# Network.net
KiCad netlist of a schematic drawn in Altium Designer
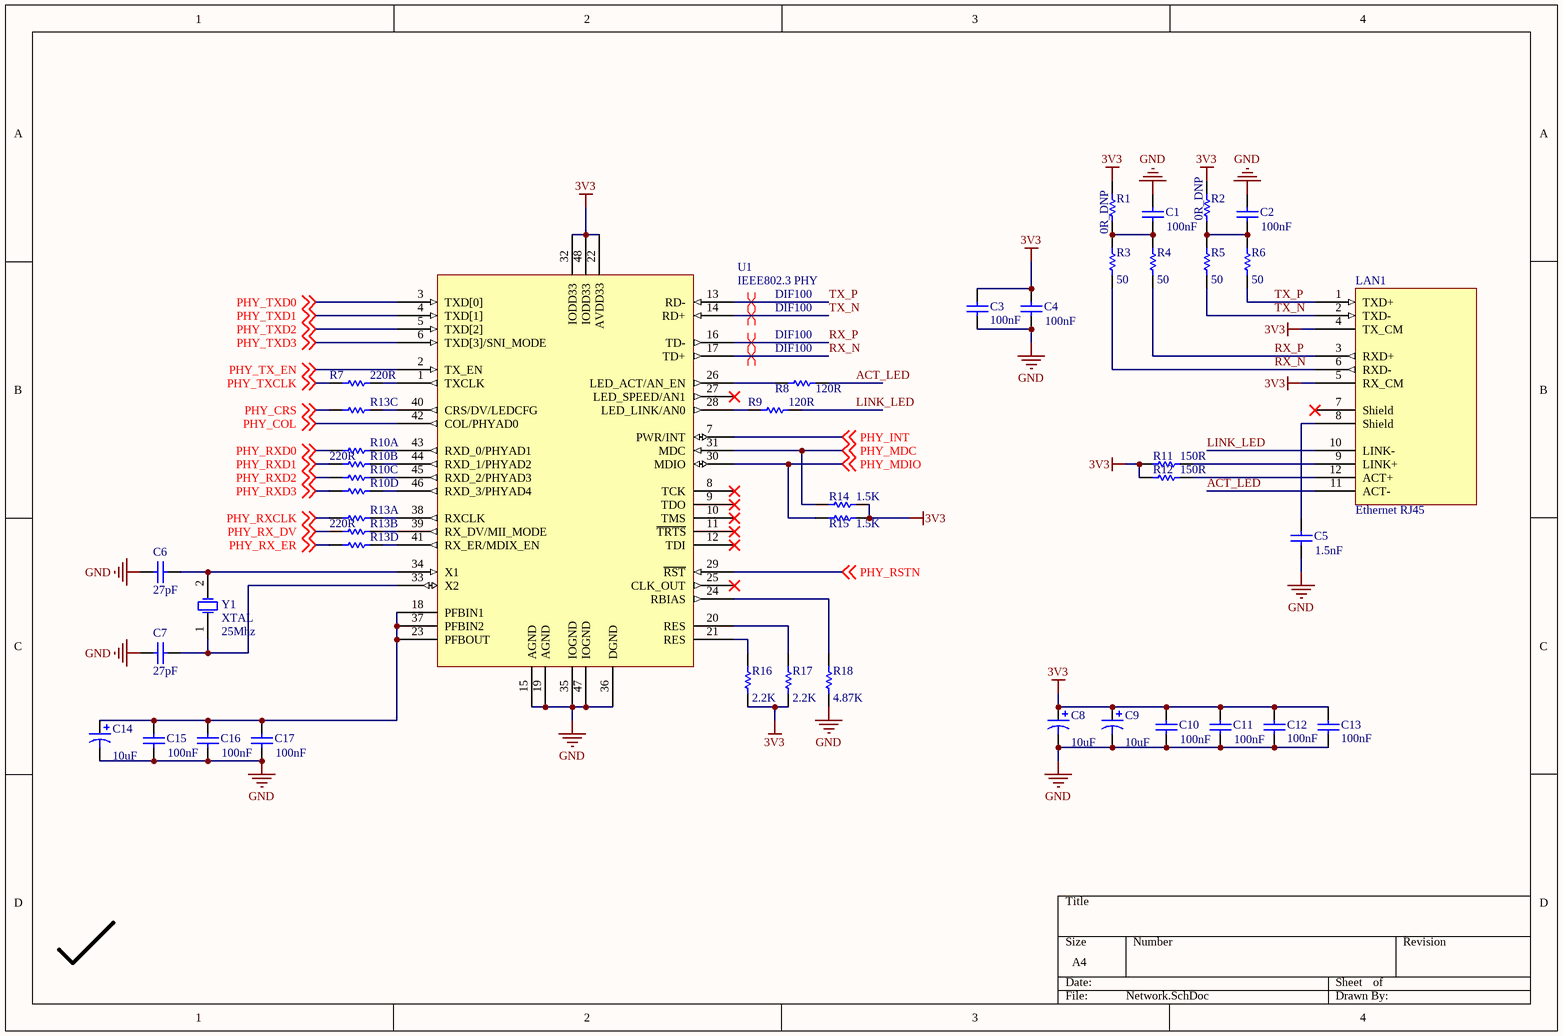
[diagram p0: Network.SchDoc]

(export (version "E")
  (design (tool "Eeschema 10.0.6"))
  (components
    (comp (ref "C1")
      (value "100nF")
      (footprint "0603PKG")
      (description "Capacitor")
      (fields (field (name "Comment") "Cap") (field (name "PUBLISHER") "Altium Limited"))
      (libsource (lib "Miscellaneous Devices") (part "Cap"))
    )
    (comp (ref "C2")
      (value "100nF")
      (footprint "0603PKG")
      (description "Capacitor")
      (fields (field (name "Comment") "Cap") (field (name "PUBLISHER") "Altium Limited"))
      (libsource (lib "Miscellaneous Devices") (part "Cap"))
    )
    (comp (ref "C3")
      (value "100nF")
      (footprint "0603PKG")
      (description "Capacitor")
      (fields (field (name "Comment") "Cap") (field (name "PUBLISHER") "Altium Limited"))
      (libsource (lib "Miscellaneous Devices") (part "Cap"))
    )
    (comp (ref "C4")
      (value "100nF")
      (footprint "0603PKG")
      (description "Capacitor")
      (fields (field (name "Comment") "Cap") (field (name "PUBLISHER") "Altium Limited"))
      (libsource (lib "Miscellaneous Devices") (part "Cap"))
    )
    (comp (ref "C5")
      (value "1.5nF")
      (footprint "C0805")
      (description "Capacitor")
      (fields (field (name "Comment") "Cap") (field (name "PUBLISHER") "Altium Limited"))
      (libsource (lib "Miscellaneous Devices") (part "Cap"))
    )
    (comp (ref "C6")
      (value "27pF")
      (footprint "C0805")
      (description "Capacitor")
      (fields (field (name "Comment") "Cap") (field (name "PUBLISHER") "Altium Limited"))
      (libsource (lib "Miscellaneous Devices") (part "Cap"))
    )
    (comp (ref "C7")
      (value "27pF")
      (footprint "C0805")
      (description "Capacitor")
      (fields (field (name "Comment") "Cap") (field (name "PUBLISHER") "Altium Limited"))
      (libsource (lib "Miscellaneous Devices") (part "Cap"))
    )
    (comp (ref "C8")
      (value "10uF")
      (footprint "3216X18N")
      (description "Polarized Capacitor (Surface Mount)")
      (fields (field (name "Comment") "Cap Pol3") (field (name "PUBLISHER") "Altium Limited"))
      (libsource (lib "Miscellaneous Devices") (part "Cap Pol3"))
    )
    (comp (ref "C9")
      (value "10uF")
      (footprint "3216X18N")
      (description "Polarized Capacitor (Surface Mount)")
      (fields (field (name "Comment") "Cap Pol3") (field (name "PUBLISHER") "Altium Limited"))
      (libsource (lib "Miscellaneous Devices") (part "Cap Pol3"))
    )
    (comp (ref "C10")
      (value "100nF")
      (footprint "0603PKG")
      (description "Capacitor")
      (fields (field (name "Comment") "Cap") (field (name "PUBLISHER") "Altium Limited"))
      (libsource (lib "Miscellaneous Devices") (part "Cap"))
    )
    (comp (ref "C11")
      (value "100nF")
      (footprint "0603PKG")
      (description "Capacitor")
      (fields (field (name "Comment") "Cap") (field (name "PUBLISHER") "Altium Limited"))
      (libsource (lib "Miscellaneous Devices") (part "Cap"))
    )
    (comp (ref "C12")
      (value "100nF")
      (footprint "0603PKG")
      (description "Capacitor")
      (fields (field (name "Comment") "Cap") (field (name "PUBLISHER") "Altium Limited"))
      (libsource (lib "Miscellaneous Devices") (part "Cap"))
    )
    (comp (ref "C13")
      (value "100nF")
      (footprint "0603PKG")
      (description "Capacitor")
      (fields (field (name "Comment") "Cap") (field (name "PUBLISHER") "Altium Limited"))
      (libsource (lib "Miscellaneous Devices") (part "Cap"))
    )
    (comp (ref "C14")
      (value "10uF")
      (footprint "3216X18N")
      (description "Polarized Capacitor (Surface Mount)")
      (fields (field (name "Comment") "Cap Pol3") (field (name "PUBLISHER") "Altium Limited"))
      (libsource (lib "Miscellaneous Devices") (part "Cap Pol3"))
    )
    (comp (ref "C15")
      (value "100nF")
      (footprint "0603PKG")
      (description "Capacitor")
      (fields (field (name "Comment") "Cap") (field (name "PUBLISHER") "Altium Limited"))
      (libsource (lib "Miscellaneous Devices") (part "Cap"))
    )
    (comp (ref "C16")
      (value "100nF")
      (footprint "0603PKG")
      (description "Capacitor")
      (fields (field (name "Comment") "Cap") (field (name "PUBLISHER") "Altium Limited"))
      (libsource (lib "Miscellaneous Devices") (part "Cap"))
    )
    (comp (ref "C17")
      (value "100nF")
      (footprint "0603PKG")
      (description "Capacitor")
      (fields (field (name "Comment") "Cap") (field (name "PUBLISHER") "Altium Limited"))
      (libsource (lib "Miscellaneous Devices") (part "Cap"))
    )
    (comp (ref "LAN1")
      (value "Ethernet RJ45")
      (footprint "RJ45")
      (libsource (lib "DE0_IntLib_Schem") (part "Ethernet_RJ45"))
    )
    (comp (ref "R1")
      (value "0R_DNP")
      (footprint "C0805")
      (description "Semiconductor Resistor")
      (fields (field (name "Comment") "Res Semi") (field (name "PUBLISHER") "Altium Limited"))
      (libsource (lib "Miscellaneous Devices") (part "Res Semi"))
    )
    (comp (ref "R2")
      (value "0R_DNP")
      (footprint "C0805")
      (description "Semiconductor Resistor")
      (fields (field (name "Comment") "Res Semi") (field (name "PUBLISHER") "Altium Limited"))
      (libsource (lib "Miscellaneous Devices") (part "Res Semi"))
    )
    (comp (ref "R3")
      (value "50")
      (footprint "C0805")
      (description "Semiconductor Resistor")
      (fields (field (name "Comment") "Res Semi") (field (name "PUBLISHER") "Altium Limited"))
      (libsource (lib "Miscellaneous Devices") (part "Res Semi"))
    )
    (comp (ref "R4")
      (value "50")
      (footprint "C0805")
      (description "Semiconductor Resistor")
      (fields (field (name "Comment") "Res Semi") (field (name "PUBLISHER") "Altium Limited"))
      (libsource (lib "Miscellaneous Devices") (part "Res Semi"))
    )
    (comp (ref "R5")
      (value "50")
      (footprint "C0805")
      (description "Semiconductor Resistor")
      (fields (field (name "Comment") "Res Semi") (field (name "PUBLISHER") "Altium Limited"))
      (libsource (lib "Miscellaneous Devices") (part "Res Semi"))
    )
    (comp (ref "R6")
      (value "50")
      (footprint "C0805")
      (description "Semiconductor Resistor")
      (fields (field (name "Comment") "Res Semi") (field (name "PUBLISHER") "Altium Limited"))
      (libsource (lib "Miscellaneous Devices") (part "Res Semi"))
    )
    (comp (ref "R7")
      (value "220R")
      (footprint "0603PKG")
      (description "Semiconductor Resistor")
      (fields (field (name "Comment") "Res Semi") (field (name "PUBLISHER") "Altium Limited"))
      (libsource (lib "Miscellaneous Devices") (part "Res Semi"))
    )
    (comp (ref "R8")
      (value "120R")
      (footprint "C0805")
      (description "Semiconductor Resistor")
      (fields (field (name "Comment") "Res Semi") (field (name "PUBLISHER") "Altium Limited"))
      (libsource (lib "Miscellaneous Devices") (part "Res Semi"))
    )
    (comp (ref "R9")
      (value "120R")
      (footprint "C0805")
      (description "Semiconductor Resistor")
      (fields (field (name "Comment") "Res Semi") (field (name "PUBLISHER") "Altium Limited"))
      (libsource (lib "Miscellaneous Devices") (part "Res Semi"))
    )
    (comp (ref "R10")
      (value "220R")
      (footprint "ARA4x0603")
      (fields (field (name "Comment") "ChipArray_4x"))
      (libsource (lib "Connector_IntLib") (part "ChipArray_4x"))
    )
    (comp (ref "R11")
      (value "150R")
      (footprint "C0805")
      (description "Semiconductor Resistor")
      (fields (field (name "Comment") "Res Semi") (field (name "PUBLISHER") "Altium Limited"))
      (libsource (lib "Miscellaneous Devices") (part "Res Semi"))
    )
    (comp (ref "R12")
      (value "150R")
      (footprint "C0805")
      (description "Semiconductor Resistor")
      (fields (field (name "Comment") "Res Semi") (field (name "PUBLISHER") "Altium Limited"))
      (libsource (lib "Miscellaneous Devices") (part "Res Semi"))
    )
    (comp (ref "R13")
      (value "220R")
      (footprint "ARA4x0603")
      (fields (field (name "Comment") "ChipArray_4x"))
      (libsource (lib "Connector_IntLib") (part "ChipArray_4x"))
    )
    (comp (ref "R14")
      (value "1.5K")
      (footprint "0603PKG")
      (description "Semiconductor Resistor")
      (fields (field (name "Comment") "Res Semi") (field (name "PUBLISHER") "Altium Limited"))
      (libsource (lib "Miscellaneous Devices") (part "Res Semi"))
    )
    (comp (ref "R15")
      (value "1.5K")
      (footprint "0603PKG")
      (description "Semiconductor Resistor")
      (fields (field (name "Comment") "Res Semi") (field (name "PUBLISHER") "Altium Limited"))
      (libsource (lib "Miscellaneous Devices") (part "Res Semi"))
    )
    (comp (ref "R16")
      (value "2.2K")
      (footprint "0603PKG")
      (description "Semiconductor Resistor")
      (fields (field (name "Comment") "Res Semi") (field (name "PUBLISHER") "Altium Limited"))
      (libsource (lib "Miscellaneous Devices") (part "Res Semi"))
    )
    (comp (ref "R17")
      (value "2.2K")
      (footprint "0603PKG")
      (description "Semiconductor Resistor")
      (fields (field (name "Comment") "Res Semi") (field (name "PUBLISHER") "Altium Limited"))
      (libsource (lib "Miscellaneous Devices") (part "Res Semi"))
    )
    (comp (ref "R18")
      (value "4.87K")
      (footprint "C1206")
      (description "Semiconductor Resistor")
      (fields (field (name "Comment") "Res Semi") (field (name "PUBLISHER") "Altium Limited"))
      (libsource (lib "Miscellaneous Devices") (part "Res Semi"))
    )
    (comp (ref "U1")
      (value "IEEE802.3 PHY")
      (footprint "LQFP48")
      (libsource (lib "Conn_Schlib") (part "DP83848C"))
    )
    (comp (ref "Y1")
      (value "XTAL")
      (footprint "SMD_Crystal")
      (description "Crystal Oscillator")
      (fields (field (name "ALTIUM_VALUE") "25Mhz") (field (name "PUBLISHER") "Altium Limited"))
      (libsource (lib "Miscellaneous Devices") (part "XTAL"))
    )
  )
  (nets
    (net (code "1") (name "/ACT_LED") (class "Default")
      (node (ref "LAN1") (pin "11") (pinfunction "ACT-_11") (pintype "power_in"))
      (node (ref "R8") (pin "2") (pinfunction "2_2") (pintype "passive"))
    )
    (net (code "2") (name "/LINK_LED") (class "Default")
      (node (ref "LAN1") (pin "10") (pinfunction "LINK-_10") (pintype "power_in"))
      (node (ref "R9") (pin "2") (pinfunction "2_2") (pintype "passive"))
    )
    (net (code "3") (name "/RX_N") (class "Default")
      (node (ref "LAN1") (pin "6") (pinfunction "RXD-_6") (pintype "output"))
      (node (ref "R3") (pin "1") (pinfunction "1_1") (pintype "passive"))
      (node (ref "U1") (pin "17") (pinfunction "TD+_17") (pintype "output"))
    )
    (net (code "4") (name "/RX_P") (class "Default")
      (node (ref "LAN1") (pin "3") (pinfunction "RXD+_3") (pintype "output"))
      (node (ref "R4") (pin "1") (pinfunction "1_1") (pintype "passive"))
      (node (ref "U1") (pin "16") (pinfunction "TD-_16") (pintype "output"))
    )
    (net (code "5") (name "/TX_N") (class "Default")
      (node (ref "LAN1") (pin "2") (pinfunction "TXD-_2") (pintype "input"))
      (node (ref "R5") (pin "1") (pinfunction "1_1") (pintype "passive"))
      (node (ref "U1") (pin "14") (pinfunction "RD+_14") (pintype "input"))
    )
    (net (code "6") (name "/TX_P") (class "Default")
      (node (ref "LAN1") (pin "1") (pinfunction "TXD+_1") (pintype "input"))
      (node (ref "R6") (pin "1") (pinfunction "1_1") (pintype "passive"))
      (node (ref "U1") (pin "13") (pinfunction "RD-_13") (pintype "input"))
    )
    (net (code "7") (name "3V3") (class "Default")
      (node (ref "C10") (pin "2") (pinfunction "2_2") (pintype "passive"))
      (node (ref "C11") (pin "2") (pinfunction "2_2") (pintype "passive"))
      (node (ref "C12") (pin "2") (pinfunction "2_2") (pintype "passive"))
      (node (ref "C13") (pin "2") (pinfunction "2_2") (pintype "passive"))
      (node (ref "C3") (pin "1") (pinfunction "1_1") (pintype "passive"))
      (node (ref "C4") (pin "2") (pinfunction "2_2") (pintype "passive"))
      (node (ref "C8") (pin "1") (pinfunction "1_1") (pintype "passive"))
      (node (ref "C9") (pin "1") (pinfunction "1_1") (pintype "passive"))
      (node (ref "LAN1") (pin "4") (pinfunction "TX_CM_4") (pintype "power_in"))
      (node (ref "LAN1") (pin "5") (pinfunction "RX_CM_5") (pintype "power_in"))
      (node (ref "R1") (pin "2") (pinfunction "2_2") (pintype "passive"))
      (node (ref "R11") (pin "1") (pinfunction "1_1") (pintype "passive"))
      (node (ref "R12") (pin "1") (pinfunction "1_1") (pintype "passive"))
      (node (ref "R14") (pin "2") (pinfunction "2_2") (pintype "passive"))
      (node (ref "R15") (pin "1") (pinfunction "1_1") (pintype "passive"))
      (node (ref "R16") (pin "1") (pinfunction "1_1") (pintype "passive"))
      (node (ref "R17") (pin "1") (pinfunction "1_1") (pintype "passive"))
      (node (ref "R2") (pin "2") (pinfunction "2_2") (pintype "passive"))
      (node (ref "U1") (pin "22") (pinfunction "AVDD33_22") (pintype "power_in"))
      (node (ref "U1") (pin "32") (pinfunction "IODD33_32") (pintype "power_in"))
      (node (ref "U1") (pin "48") (pinfunction "IODD33_48") (pintype "power_in"))
    )
    (net (code "8") (name "GND") (class "Default")
      (node (ref "C1") (pin "2") (pinfunction "2_2") (pintype "passive"))
      (node (ref "C10") (pin "1") (pinfunction "1_1") (pintype "passive"))
      (node (ref "C11") (pin "1") (pinfunction "1_1") (pintype "passive"))
      (node (ref "C12") (pin "1") (pinfunction "1_1") (pintype "passive"))
      (node (ref "C13") (pin "1") (pinfunction "1_1") (pintype "passive"))
      (node (ref "C14") (pin "2") (pinfunction "2_2") (pintype "passive"))
      (node (ref "C15") (pin "1") (pinfunction "1_1") (pintype "passive"))
      (node (ref "C16") (pin "1") (pinfunction "1_1") (pintype "passive"))
      (node (ref "C17") (pin "1") (pinfunction "1_1") (pintype "passive"))
      (node (ref "C2") (pin "2") (pinfunction "2_2") (pintype "passive"))
      (node (ref "C3") (pin "2") (pinfunction "2_2") (pintype "passive"))
      (node (ref "C4") (pin "1") (pinfunction "1_1") (pintype "passive"))
      (node (ref "C5") (pin "1") (pinfunction "1_1") (pintype "passive"))
      (node (ref "C6") (pin "2") (pinfunction "2_2") (pintype "passive"))
      (node (ref "C7") (pin "2") (pinfunction "2_2") (pintype "passive"))
      (node (ref "C8") (pin "2") (pinfunction "2_2") (pintype "passive"))
      (node (ref "C9") (pin "2") (pinfunction "2_2") (pintype "passive"))
      (node (ref "R18") (pin "1") (pinfunction "1_1") (pintype "passive"))
      (node (ref "U1") (pin "15") (pinfunction "AGND_15") (pintype "power_in"))
      (node (ref "U1") (pin "19") (pinfunction "AGND_19") (pintype "power_in"))
      (node (ref "U1") (pin "35") (pinfunction "IOGND_35") (pintype "power_in"))
      (node (ref "U1") (pin "36") (pinfunction "DGND_36") (pintype "power_in"))
      (node (ref "U1") (pin "47") (pinfunction "IOGND_47") (pintype "power_in"))
    )
    (net (code "9") (name "Net-(C1-Pad1)") (class "Default")
      (node (ref "C1") (pin "1") (pinfunction "1_1") (pintype "passive"))
      (node (ref "R1") (pin "1") (pinfunction "1_1") (pintype "passive"))
      (node (ref "R3") (pin "2") (pinfunction "2_2") (pintype "passive"))
      (node (ref "R4") (pin "2") (pinfunction "2_2") (pintype "passive"))
    )
    (net (code "10") (name "Net-(C2-Pad1)") (class "Default")
      (node (ref "C2") (pin "1") (pinfunction "1_1") (pintype "passive"))
      (node (ref "R2") (pin "1") (pinfunction "1_1") (pintype "passive"))
      (node (ref "R5") (pin "2") (pinfunction "2_2") (pintype "passive"))
      (node (ref "R6") (pin "2") (pinfunction "2_2") (pintype "passive"))
    )
    (net (code "11") (name "Net-(C5-Pad2)") (class "Default")
      (node (ref "C5") (pin "2") (pinfunction "2_2") (pintype "passive"))
      (node (ref "LAN1") (pin "8") (pinfunction "Shield_8") (pintype "passive"))
    )
    (net (code "12") (name "Net-(LAN1-ACT+)") (class "Default")
      (node (ref "LAN1") (pin "12") (pinfunction "ACT+_12") (pintype "power_in"))
      (node (ref "R12") (pin "2") (pinfunction "2_2") (pintype "passive"))
    )
    (net (code "13") (name "Net-(LAN1-LINK+)") (class "Default")
      (node (ref "LAN1") (pin "9") (pinfunction "LINK+_9") (pintype "power_in"))
      (node (ref "R11") (pin "2") (pinfunction "2_2") (pintype "passive"))
    )
    (net (code "14") (name "Net-(R16-Pad2)") (class "Default")
      (node (ref "R16") (pin "2") (pinfunction "2_2") (pintype "passive"))
      (node (ref "U1") (pin "21") (pinfunction "RES_21") (pintype "passive"))
    )
    (net (code "15") (name "Net-(R17-Pad2)") (class "Default")
      (node (ref "R17") (pin "2") (pinfunction "2_2") (pintype "passive"))
      (node (ref "U1") (pin "20") (pinfunction "RES_20") (pintype "passive"))
    )
    (net (code "16") (name "Net-(U1-CRS{slash}DV{slash}LEDCFG)") (class "Default")
      (node (ref "R13") (pin "6") (pinfunction "R3_6") (pintype "passive"))
      (node (ref "U1") (pin "40") (pinfunction "CRS/DV/LEDCFG_40") (pintype "output"))
    )
    (net (code "17") (name "Net-(U1-LED_ACT{slash}AN_EN)") (class "Default")
      (node (ref "R8") (pin "1") (pinfunction "1_1") (pintype "passive"))
      (node (ref "U1") (pin "26") (pinfunction "LED_ACT/AN_EN_26") (pintype "output"))
    )
    (net (code "18") (name "Net-(U1-LED_LINK{slash}AN0)") (class "Default")
      (node (ref "R9") (pin "1") (pinfunction "1_1") (pintype "passive"))
      (node (ref "U1") (pin "28") (pinfunction "LED_LINK/AN0_28") (pintype "output"))
    )
    (net (code "19") (name "Net-(U1-PFBIN1)") (class "Default")
      (node (ref "C14") (pin "1") (pinfunction "1_1") (pintype "passive"))
      (node (ref "C15") (pin "2") (pinfunction "2_2") (pintype "passive"))
      (node (ref "C16") (pin "2") (pinfunction "2_2") (pintype "passive"))
      (node (ref "C17") (pin "2") (pinfunction "2_2") (pintype "passive"))
      (node (ref "U1") (pin "18") (pinfunction "PFBIN1_18") (pintype "passive"))
      (node (ref "U1") (pin "23") (pinfunction "PFBOUT_23") (pintype "passive"))
      (node (ref "U1") (pin "37") (pinfunction "PFBIN2_37") (pintype "passive"))
    )
    (net (code "20") (name "Net-(U1-RBIAS)") (class "Default")
      (node (ref "R18") (pin "2") (pinfunction "2_2") (pintype "passive"))
      (node (ref "U1") (pin "24") (pinfunction "RBIAS_24") (pintype "output"))
    )
    (net (code "21") (name "Net-(U1-RXCLK)") (class "Default")
      (node (ref "R13") (pin "8") (pinfunction "R1_8") (pintype "passive"))
      (node (ref "U1") (pin "38") (pinfunction "RXCLK_38") (pintype "output"))
    )
    (net (code "22") (name "Net-(U1-RXD_0{slash}PHYAD1)") (class "Default")
      (node (ref "R10") (pin "8") (pinfunction "R1_8") (pintype "passive"))
      (node (ref "U1") (pin "43") (pinfunction "RXD_0/PHYAD1_43") (pintype "output"))
    )
    (net (code "23") (name "Net-(U1-RXD_1{slash}PHYAD2)") (class "Default")
      (node (ref "R10") (pin "7") (pinfunction "R2_7") (pintype "passive"))
      (node (ref "U1") (pin "44") (pinfunction "RXD_1/PHYAD2_44") (pintype "output"))
    )
    (net (code "24") (name "Net-(U1-RXD_2{slash}PHYAD3)") (class "Default")
      (node (ref "R10") (pin "6") (pinfunction "R3_6") (pintype "passive"))
      (node (ref "U1") (pin "45") (pinfunction "RXD_2/PHYAD3_45") (pintype "output"))
    )
    (net (code "25") (name "Net-(U1-RXD_3{slash}PHYAD4)") (class "Default")
      (node (ref "R10") (pin "5") (pinfunction "R4_5") (pintype "passive"))
      (node (ref "U1") (pin "46") (pinfunction "RXD_3/PHYAD4_46") (pintype "output"))
    )
    (net (code "26") (name "Net-(U1-RX_DV{slash}MII_MODE)") (class "Default")
      (node (ref "R13") (pin "7") (pinfunction "R2_7") (pintype "passive"))
      (node (ref "U1") (pin "39") (pinfunction "RX_DV/MII_MODE_39") (pintype "output"))
    )
    (net (code "27") (name "Net-(U1-RX_ER{slash}MDIX_EN)") (class "Default")
      (node (ref "R13") (pin "5") (pinfunction "R4_5") (pintype "passive"))
      (node (ref "U1") (pin "41") (pinfunction "RX_ER/MDIX_EN_41") (pintype "output"))
    )
    (net (code "28") (name "Net-(U1-TXCLK)") (class "Default")
      (node (ref "R7") (pin "2") (pinfunction "2_2") (pintype "passive"))
      (node (ref "U1") (pin "1") (pinfunction "TXCLK_1") (pintype "output"))
    )
    (net (code "29") (name "Net-(U1-X1)") (class "Default")
      (node (ref "C6") (pin "1") (pinfunction "1_1") (pintype "passive"))
      (node (ref "U1") (pin "34") (pinfunction "X1_34") (pintype "input"))
      (node (ref "Y1") (pin "2") (pinfunction "OSC2_2") (pintype "passive"))
    )
    (net (code "30") (name "Net-(U1-X2)") (class "Default")
      (node (ref "C7") (pin "1") (pinfunction "1_1") (pintype "passive"))
      (node (ref "U1") (pin "33") (pinfunction "X2_33") (pintype "bidirectional"))
      (node (ref "Y1") (pin "1") (pinfunction "OSC1_1") (pintype "passive"))
    )
    (net (code "31") (name "PHY_COL") (class "Default")
      (node (ref "U1") (pin "42") (pinfunction "COL/PHYAD0_42") (pintype "output"))
    )
    (net (code "32") (name "PHY_CRS") (class "Default")
      (node (ref "R13") (pin "3") (pinfunction "R3_3") (pintype "passive"))
    )
    (net (code "33") (name "PHY_INT") (class "Default")
      (node (ref "U1") (pin "7") (pinfunction "PWR/INT_7") (pintype "bidirectional"))
    )
    (net (code "34") (name "PHY_MDC") (class "Default")
      (node (ref "R14") (pin "1") (pinfunction "1_1") (pintype "passive"))
      (node (ref "U1") (pin "31") (pinfunction "MDC_31") (pintype "input"))
    )
    (net (code "35") (name "PHY_MDIO") (class "Default")
      (node (ref "R15") (pin "2") (pinfunction "2_2") (pintype "passive"))
      (node (ref "U1") (pin "30") (pinfunction "MDIO_30") (pintype "bidirectional"))
    )
    (net (code "36") (name "PHY_RSTN") (class "Default")
      (node (ref "U1") (pin "29") (pinfunction "~{RST}_29") (pintype "input"))
    )
    (net (code "37") (name "PHY_RXCLK") (class "Default")
      (node (ref "R13") (pin "1") (pinfunction "R1_1") (pintype "passive"))
    )
    (net (code "38") (name "PHY_RXD0") (class "Default")
      (node (ref "R10") (pin "1") (pinfunction "R1_1") (pintype "passive"))
    )
    (net (code "39") (name "PHY_RXD1") (class "Default")
      (node (ref "R10") (pin "2") (pinfunction "R2_2") (pintype "passive"))
    )
    (net (code "40") (name "PHY_RXD2") (class "Default")
      (node (ref "R10") (pin "3") (pinfunction "R3_3") (pintype "passive"))
    )
    (net (code "41") (name "PHY_RXD3") (class "Default")
      (node (ref "R10") (pin "4") (pinfunction "R4_4") (pintype "passive"))
    )
    (net (code "42") (name "PHY_RX_DV") (class "Default")
      (node (ref "R13") (pin "2") (pinfunction "R2_2") (pintype "passive"))
    )
    (net (code "43") (name "PHY_RX_ER") (class "Default")
      (node (ref "R13") (pin "4") (pinfunction "R4_4") (pintype "passive"))
    )
    (net (code "44") (name "PHY_TXCLK") (class "Default")
      (node (ref "R7") (pin "1") (pinfunction "1_1") (pintype "passive"))
    )
    (net (code "45") (name "PHY_TXD0") (class "Default")
      (node (ref "U1") (pin "3") (pinfunction "TXD[0]_3") (pintype "input"))
    )
    (net (code "46") (name "PHY_TXD1") (class "Default")
      (node (ref "U1") (pin "4") (pinfunction "TXD[1]_4") (pintype "input"))
    )
    (net (code "47") (name "PHY_TXD2") (class "Default")
      (node (ref "U1") (pin "5") (pinfunction "TXD[2]_5") (pintype "input"))
    )
    (net (code "48") (name "PHY_TXD3") (class "Default")
      (node (ref "U1") (pin "6") (pinfunction "TXD[3]/SNI_MODE_6") (pintype "input"))
    )
    (net (code "49") (name "PHY_TX_EN") (class "Default")
      (node (ref "U1") (pin "2") (pinfunction "TX_EN_2") (pintype "input"))
    )
    (net (code "50") (name "unconnected-(LAN1-Shield-Pad7)") (class "Default")
      (node (ref "LAN1") (pin "7") (pinfunction "Shield_7") (pintype "passive+no_connect"))
    )
    (net (code "51") (name "unconnected-(U1-CLK_OUT-Pad25)") (class "Default")
      (node (ref "U1") (pin "25") (pinfunction "CLK_OUT_25") (pintype "output+no_connect"))
    )
    (net (code "52") (name "unconnected-(U1-LED_SPEED{slash}AN1-Pad27)") (class "Default")
      (node (ref "U1") (pin "27") (pinfunction "LED_SPEED/AN1_27") (pintype "output+no_connect"))
    )
    (net (code "53") (name "unconnected-(U1-TCK-Pad8)") (class "Default")
      (node (ref "U1") (pin "8") (pinfunction "TCK_8") (pintype "passive+no_connect"))
    )
    (net (code "54") (name "unconnected-(U1-TDI-Pad12)") (class "Default")
      (node (ref "U1") (pin "12") (pinfunction "TDI_12") (pintype "passive+no_connect"))
    )
    (net (code "55") (name "unconnected-(U1-TDO-Pad9)") (class "Default")
      (node (ref "U1") (pin "9") (pinfunction "TDO_9") (pintype "passive+no_connect"))
    )
    (net (code "56") (name "unconnected-(U1-TMS-Pad10)") (class "Default")
      (node (ref "U1") (pin "10") (pinfunction "TMS_10") (pintype "passive+no_connect"))
    )
    (net (code "57") (name "unconnected-(U1-~{TRTS}-Pad11)") (class "Default")
      (node (ref "U1") (pin "11") (pinfunction "~{TRTS}_11") (pintype "passive+no_connect"))
    )
  )
)
